# analog.net
KiCad netlist of a schematic drawn in Altium Designer
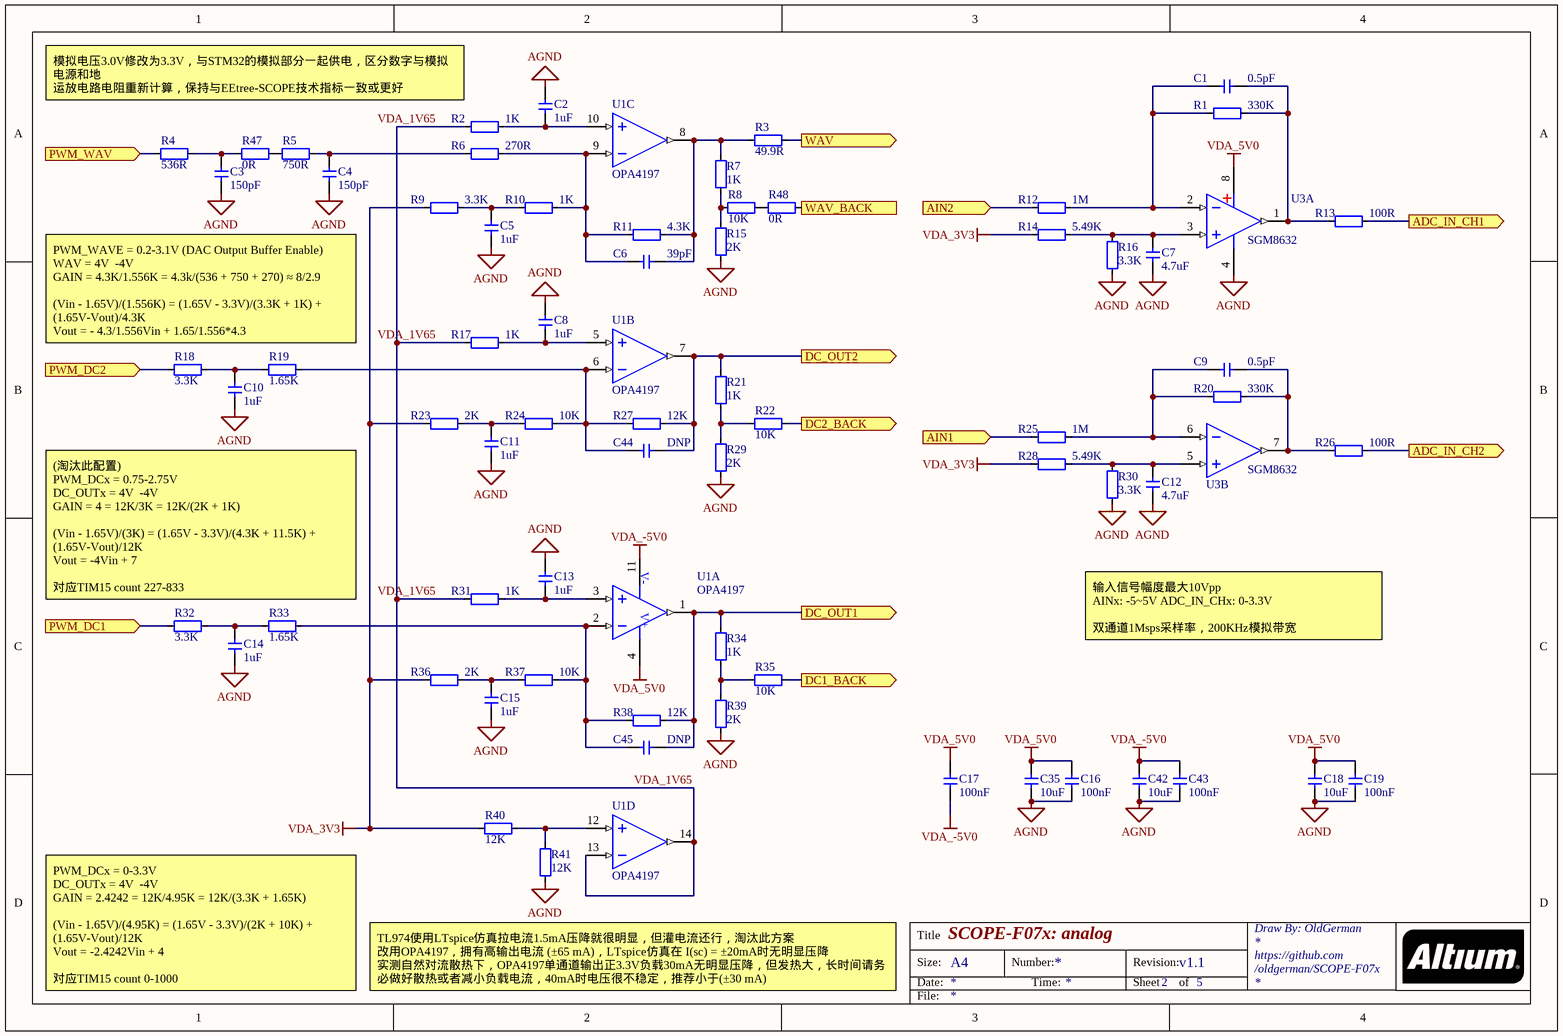
[diagram p0: analog.SchDoc]

(export (version "E")
  (design (tool "Eeschema 10.0.6"))
  (components
    (comp (ref "C1")
      (value "0.5pF")
      (footprint "C0402")
      (description "Capacitor")
      (libsource (lib "ODG_AD_Lib") (part "CAP"))
    )
    (comp (ref "C2")
      (value "1uF")
      (footprint "C0402")
      (description "Capacitor")
      (libsource (lib "ODG_AD_Lib") (part "CAP"))
    )
    (comp (ref "C3")
      (value "150pF")
      (footprint "C0402")
      (description "Capacitor")
      (libsource (lib "ODG_AD_Lib") (part "CAP"))
    )
    (comp (ref "C4")
      (value "150pF")
      (footprint "C0402")
      (description "Capacitor")
      (libsource (lib "ODG_AD_Lib") (part "CAP"))
    )
    (comp (ref "C5")
      (value "1uF")
      (footprint "C0402")
      (description "Capacitor")
      (libsource (lib "ODG_AD_Lib") (part "CAP"))
    )
    (comp (ref "C6")
      (value "39pF")
      (footprint "C0402")
      (description "Capacitor")
      (libsource (lib "ODG_AD_Lib") (part "CAP"))
    )
    (comp (ref "C7")
      (value "4.7uF")
      (footprint "C0402")
      (description "Capacitor")
      (libsource (lib "ODG_AD_Lib") (part "CAP"))
    )
    (comp (ref "C8")
      (value "1uF")
      (footprint "C0402")
      (description "Capacitor")
      (libsource (lib "ODG_AD_Lib") (part "CAP"))
    )
    (comp (ref "C9")
      (value "0.5pF")
      (footprint "C0402")
      (description "Capacitor")
      (libsource (lib "ODG_AD_Lib") (part "CAP"))
    )
    (comp (ref "C10")
      (value "1uF")
      (footprint "C0402")
      (description "Capacitor")
      (libsource (lib "ODG_AD_Lib") (part "CAP"))
    )
    (comp (ref "C11")
      (value "1uF")
      (footprint "C0402")
      (description "Capacitor")
      (libsource (lib "ODG_AD_Lib") (part "CAP"))
    )
    (comp (ref "C12")
      (value "4.7uF")
      (footprint "C0402")
      (description "Capacitor")
      (libsource (lib "ODG_AD_Lib") (part "CAP"))
    )
    (comp (ref "C13")
      (value "1uF")
      (footprint "C0402")
      (description "Capacitor")
      (libsource (lib "ODG_AD_Lib") (part "CAP"))
    )
    (comp (ref "C14")
      (value "1uF")
      (footprint "C0402")
      (description "Capacitor")
      (libsource (lib "ODG_AD_Lib") (part "CAP"))
    )
    (comp (ref "C15")
      (value "1uF")
      (footprint "C0402")
      (description "Capacitor")
      (libsource (lib "ODG_AD_Lib") (part "CAP"))
    )
    (comp (ref "C16")
      (value "100nF")
      (footprint "C0402")
      (description "Capacitor")
      (libsource (lib "ODG_AD_Lib") (part "CAP"))
    )
    (comp (ref "C17")
      (value "100nF")
      (footprint "C0402")
      (description "Capacitor")
      (libsource (lib "ODG_AD_Lib") (part "CAP"))
    )
    (comp (ref "C18")
      (value "10uF")
      (footprint "C0402")
      (description "Capacitor")
      (libsource (lib "ODG_AD_Lib") (part "CAP"))
    )
    (comp (ref "C19")
      (value "100nF")
      (footprint "C0402")
      (description "Capacitor")
      (libsource (lib "ODG_AD_Lib") (part "CAP"))
    )
    (comp (ref "C35")
      (value "10uF")
      (footprint "C0402")
      (description "Capacitor")
      (libsource (lib "ODG_AD_Lib") (part "CAP"))
    )
    (comp (ref "C42")
      (value "10uF")
      (footprint "C0402")
      (description "Capacitor")
      (libsource (lib "ODG_AD_Lib") (part "CAP"))
    )
    (comp (ref "C43")
      (value "100nF")
      (footprint "C0402")
      (description "Capacitor")
      (libsource (lib "ODG_AD_Lib") (part "CAP"))
    )
    (comp (ref "C44")
      (value "DNP")
      (footprint "C0402")
      (description "Capacitor")
      (libsource (lib "ODG_AD_Lib") (part "CAP"))
    )
    (comp (ref "C45")
      (value "DNP")
      (footprint "C0402")
      (description "Capacitor")
      (libsource (lib "ODG_AD_Lib") (part "CAP"))
    )
    (comp (ref "R1")
      (value "330K")
      (footprint "R0402")
      (description "Resistor")
      (libsource (lib "ODG_AD_Lib") (part "RES"))
    )
    (comp (ref "R2")
      (value "1K")
      (footprint "R0402")
      (description "Resistor")
      (libsource (lib "ODG_AD_Lib") (part "RES"))
    )
    (comp (ref "R3")
      (value "49.9R")
      (footprint "R0402")
      (description "Resistor")
      (libsource (lib "ODG_AD_Lib") (part "RES"))
    )
    (comp (ref "R4")
      (value "536R")
      (footprint "R0402")
      (description "Resistor")
      (libsource (lib "ODG_AD_Lib") (part "RES"))
    )
    (comp (ref "R5")
      (value "750R")
      (footprint "R0402")
      (description "Resistor")
      (libsource (lib "ODG_AD_Lib") (part "RES"))
    )
    (comp (ref "R6")
      (value "270R")
      (footprint "R0402")
      (description "Resistor")
      (libsource (lib "ODG_AD_Lib") (part "RES"))
    )
    (comp (ref "R7")
      (value "1K")
      (footprint "R0402")
      (description "Resistor")
      (libsource (lib "") (part "RES_1"))
    )
    (comp (ref "R8")
      (value "10K")
      (footprint "R0402")
      (description "Resistor")
      (libsource (lib "") (part "RES_2"))
    )
    (comp (ref "R9")
      (value "3.3K")
      (footprint "R0402")
      (description "Resistor")
      (libsource (lib "ODG_AD_Lib") (part "RES"))
    )
    (comp (ref "R10")
      (value "1K")
      (footprint "R0402")
      (description "Resistor")
      (libsource (lib "ODG_AD_Lib") (part "RES"))
    )
    (comp (ref "R11")
      (value "4.3K")
      (footprint "R0402")
      (description "Resistor")
      (libsource (lib "ODG_AD_Lib") (part "RES"))
    )
    (comp (ref "R12")
      (value "1M")
      (footprint "R0402")
      (description "Resistor")
      (libsource (lib "ODG_AD_Lib") (part "RES"))
    )
    (comp (ref "R13")
      (value "100R")
      (footprint "R0402")
      (description "Resistor")
      (libsource (lib "ODG_AD_Lib") (part "RES"))
    )
    (comp (ref "R14")
      (value "5.49K")
      (footprint "R0402")
      (description "Resistor")
      (libsource (lib "ODG_AD_Lib") (part "RES"))
    )
    (comp (ref "R15")
      (value "2K")
      (footprint "R0402")
      (description "Resistor")
      (libsource (lib "") (part "RES_1"))
    )
    (comp (ref "R16")
      (value "3.3K")
      (footprint "R0402")
      (description "Resistor")
      (libsource (lib "") (part "RES_1"))
    )
    (comp (ref "R17")
      (value "1K")
      (footprint "R0402")
      (description "Resistor")
      (libsource (lib "ODG_AD_Lib") (part "RES"))
    )
    (comp (ref "R18")
      (value "3.3K")
      (footprint "R0402")
      (description "Resistor")
      (libsource (lib "ODG_AD_Lib") (part "RES"))
    )
    (comp (ref "R19")
      (value "1.65K")
      (footprint "R0402")
      (description "Resistor")
      (libsource (lib "ODG_AD_Lib") (part "RES"))
    )
    (comp (ref "R20")
      (value "330K")
      (footprint "R0402")
      (description "Resistor")
      (libsource (lib "ODG_AD_Lib") (part "RES"))
    )
    (comp (ref "R21")
      (value "1K")
      (footprint "R0402")
      (description "Resistor")
      (libsource (lib "") (part "RES_1"))
    )
    (comp (ref "R22")
      (value "10K")
      (footprint "R0402")
      (description "Resistor")
      (libsource (lib "") (part "RES_2"))
    )
    (comp (ref "R23")
      (value "2K")
      (footprint "R0402")
      (description "Resistor")
      (libsource (lib "ODG_AD_Lib") (part "RES"))
    )
    (comp (ref "R24")
      (value "10K")
      (footprint "R0402")
      (description "Resistor")
      (libsource (lib "ODG_AD_Lib") (part "RES"))
    )
    (comp (ref "R25")
      (value "1M")
      (footprint "R0402")
      (description "Resistor")
      (libsource (lib "ODG_AD_Lib") (part "RES"))
    )
    (comp (ref "R26")
      (value "100R")
      (footprint "R0402")
      (description "Resistor")
      (libsource (lib "ODG_AD_Lib") (part "RES"))
    )
    (comp (ref "R27")
      (value "12K")
      (footprint "R0402")
      (description "Resistor")
      (libsource (lib "ODG_AD_Lib") (part "RES"))
    )
    (comp (ref "R28")
      (value "5.49K")
      (footprint "R0402")
      (description "Resistor")
      (libsource (lib "ODG_AD_Lib") (part "RES"))
    )
    (comp (ref "R29")
      (value "2K")
      (footprint "R0402")
      (description "Resistor")
      (libsource (lib "") (part "RES_1"))
    )
    (comp (ref "R30")
      (value "3.3K")
      (footprint "R0402")
      (description "Resistor")
      (libsource (lib "") (part "RES_1"))
    )
    (comp (ref "R31")
      (value "1K")
      (footprint "R0402")
      (description "Resistor")
      (libsource (lib "ODG_AD_Lib") (part "RES"))
    )
    (comp (ref "R32")
      (value "3.3K")
      (footprint "R0402")
      (description "Resistor")
      (libsource (lib "ODG_AD_Lib") (part "RES"))
    )
    (comp (ref "R33")
      (value "1.65K")
      (footprint "R0402")
      (description "Resistor")
      (libsource (lib "ODG_AD_Lib") (part "RES"))
    )
    (comp (ref "R34")
      (value "1K")
      (footprint "R0402")
      (description "Resistor")
      (libsource (lib "") (part "RES_1"))
    )
    (comp (ref "R35")
      (value "10K")
      (footprint "R0402")
      (description "Resistor")
      (libsource (lib "") (part "RES_2"))
    )
    (comp (ref "R36")
      (value "2K")
      (footprint "R0402")
      (description "Resistor")
      (libsource (lib "ODG_AD_Lib") (part "RES"))
    )
    (comp (ref "R37")
      (value "10K")
      (footprint "R0402")
      (description "Resistor")
      (libsource (lib "ODG_AD_Lib") (part "RES"))
    )
    (comp (ref "R38")
      (value "12K")
      (footprint "R0402")
      (description "Resistor")
      (libsource (lib "ODG_AD_Lib") (part "RES"))
    )
    (comp (ref "R39")
      (value "2K")
      (footprint "R0402")
      (description "Resistor")
      (libsource (lib "") (part "RES_1"))
    )
    (comp (ref "R40")
      (value "12K")
      (footprint "R0402")
      (description "Resistor")
      (libsource (lib "ODG_AD_Lib") (part "RES"))
    )
    (comp (ref "R41")
      (value "12K")
      (footprint "R0402")
      (description "Resistor")
      (libsource (lib "") (part "RES_1"))
    )
    (comp (ref "R47")
      (value "0R")
      (footprint "R0805")
      (description "Resistor")
      (libsource (lib "ODG_AD_Lib") (part "RES"))
    )
    (comp (ref "R48")
      (value "0R")
      (footprint "R0805")
      (description "Resistor")
      (libsource (lib "ODG_AD_Lib") (part "RES"))
    )
    (comp (ref "U1")
      (value "OPA4197")
      (footprint "ON SEMI TSSOP-14 948G")
      (fields
        (field (name "PART NUMBER") "ADA4622-4")
        (field (name "MANUFACTURER") "Analog Devices")
        (field (name "MANUFACTURER PART NUMBER") "ADA4622-4ACPZ-RL")
        (field (name "PUBLISHER") "Nordic Semiconductor")
      )
      (libsource (lib "ODG_Project") (part "OPA4140AIPWR"))
    )
    (comp (ref "U3")
      (value "SGM8632")
      (footprint "ANALOG DEV SOIC-8 R8")
      (fields (field (name "版权归属") "源创客"))
      (libsource (lib "ODG_AD_Lib") (part "AD8542"))
    )
  )
  (nets
    (net (code "1") (name "/ADC_IN_CH1") (class "Default")
      (node (ref "R13") (pin "2") (pinfunction "2_2") (pintype "passive"))
    )
    (net (code "2") (name "/ADC_IN_CH2") (class "Default")
      (node (ref "R26") (pin "2") (pinfunction "2_2") (pintype "passive"))
    )
    (net (code "3") (name "/AIN1") (class "Default")
      (node (ref "R25") (pin "1") (pinfunction "1_1") (pintype "passive"))
    )
    (net (code "4") (name "/AIN2") (class "Default")
      (node (ref "R12") (pin "1") (pinfunction "1_1") (pintype "passive"))
    )
    (net (code "5") (name "/DC1_BACK") (class "Default")
      (node (ref "R35") (pin "1") (pinfunction "1_1") (pintype "passive"))
    )
    (net (code "6") (name "/DC2_BACK") (class "Default")
      (node (ref "R22") (pin "1") (pinfunction "1_1") (pintype "passive"))
    )
    (net (code "7") (name "/DC_OUT1") (class "Default")
      (node (ref "C45") (pin "1") (pinfunction "1_1") (pintype "passive"))
      (node (ref "R34") (pin "2") (pinfunction "2_2") (pintype "passive"))
      (node (ref "R38") (pin "2") (pinfunction "2_2") (pintype "passive"))
      (node (ref "U1") (pin "1") (pinfunction "OUTA_1") (pintype "output"))
    )
    (net (code "8") (name "/DC_OUT2") (class "Default")
      (node (ref "C44") (pin "1") (pinfunction "1_1") (pintype "passive"))
      (node (ref "R21") (pin "2") (pinfunction "2_2") (pintype "passive"))
      (node (ref "R27") (pin "2") (pinfunction "2_2") (pintype "passive"))
      (node (ref "U1") (pin "7") (pinfunction "OUTB_7") (pintype "output"))
    )
    (net (code "9") (name "/PWM_DC1") (class "Default")
      (node (ref "R32") (pin "1") (pinfunction "1_1") (pintype "passive"))
    )
    (net (code "10") (name "/PWM_DC2") (class "Default")
      (node (ref "R18") (pin "1") (pinfunction "1_1") (pintype "passive"))
    )
    (net (code "11") (name "/PWM_WAV") (class "Default")
      (node (ref "R4") (pin "1") (pinfunction "1_1") (pintype "passive"))
    )
    (net (code "12") (name "/VDA_1V65") (class "Default")
      (node (ref "R17") (pin "1") (pinfunction "1_1") (pintype "passive"))
      (node (ref "R2") (pin "1") (pinfunction "1_1") (pintype "passive"))
      (node (ref "R31") (pin "1") (pinfunction "1_1") (pintype "passive"))
      (node (ref "U1") (pin "13") (pinfunction "IN_D-_13") (pintype "input"))
      (node (ref "U1") (pin "14") (pinfunction "OUTD_14") (pintype "output"))
    )
    (net (code "13") (name "/WAV") (class "Default")
      (node (ref "R3") (pin "2") (pinfunction "2_2") (pintype "passive"))
    )
    (net (code "14") (name "/WAV_BACK") (class "Default")
      (node (ref "R48") (pin "2") (pinfunction "2_2") (pintype "passive"))
    )
    (net (code "15") (name "AGND") (class "Default")
      (node (ref "C10") (pin "1") (pinfunction "1_1") (pintype "passive"))
      (node (ref "C11") (pin "1") (pinfunction "1_1") (pintype "passive"))
      (node (ref "C12") (pin "1") (pinfunction "1_1") (pintype "passive"))
      (node (ref "C13") (pin "2") (pinfunction "2_2") (pintype "passive"))
      (node (ref "C14") (pin "1") (pinfunction "1_1") (pintype "passive"))
      (node (ref "C15") (pin "1") (pinfunction "1_1") (pintype "passive"))
      (node (ref "C16") (pin "1") (pinfunction "1_1") (pintype "passive"))
      (node (ref "C18") (pin "1") (pinfunction "1_1") (pintype "passive"))
      (node (ref "C19") (pin "1") (pinfunction "1_1") (pintype "passive"))
      (node (ref "C2") (pin "2") (pinfunction "2_2") (pintype "passive"))
      (node (ref "C3") (pin "1") (pinfunction "1_1") (pintype "passive"))
      (node (ref "C35") (pin "1") (pinfunction "1_1") (pintype "passive"))
      (node (ref "C4") (pin "1") (pinfunction "1_1") (pintype "passive"))
      (node (ref "C42") (pin "1") (pinfunction "1_1") (pintype "passive"))
      (node (ref "C43") (pin "1") (pinfunction "1_1") (pintype "passive"))
      (node (ref "C5") (pin "1") (pinfunction "1_1") (pintype "passive"))
      (node (ref "C7") (pin "1") (pinfunction "1_1") (pintype "passive"))
      (node (ref "C8") (pin "2") (pinfunction "2_2") (pintype "passive"))
      (node (ref "R15") (pin "1") (pinfunction "1_1") (pintype "passive"))
      (node (ref "R16") (pin "1") (pinfunction "1_1") (pintype "passive"))
      (node (ref "R29") (pin "1") (pinfunction "1_1") (pintype "passive"))
      (node (ref "R30") (pin "1") (pinfunction "1_1") (pintype "passive"))
      (node (ref "R39") (pin "1") (pinfunction "1_1") (pintype "passive"))
      (node (ref "R41") (pin "1") (pinfunction "1_1") (pintype "passive"))
      (node (ref "U3") (pin "4") (pinfunction "V-_4") (pintype "power_in"))
    )
    (net (code "16") (name "Net-(C3-Pad2)") (class "Default")
      (node (ref "C3") (pin "2") (pinfunction "2_2") (pintype "passive"))
      (node (ref "R4") (pin "2") (pinfunction "2_2") (pintype "passive"))
      (node (ref "R47") (pin "1") (pinfunction "1_1") (pintype "passive"))
    )
    (net (code "17") (name "Net-(C4-Pad2)") (class "Default")
      (node (ref "C4") (pin "2") (pinfunction "2_2") (pintype "passive"))
      (node (ref "R5") (pin "2") (pinfunction "2_2") (pintype "passive"))
      (node (ref "R6") (pin "1") (pinfunction "1_1") (pintype "passive"))
    )
    (net (code "18") (name "Net-(C5-Pad2)") (class "Default")
      (node (ref "C5") (pin "2") (pinfunction "2_2") (pintype "passive"))
      (node (ref "R10") (pin "1") (pinfunction "1_1") (pintype "passive"))
      (node (ref "R9") (pin "2") (pinfunction "2_2") (pintype "passive"))
    )
    (net (code "19") (name "Net-(C10-Pad2)") (class "Default")
      (node (ref "C10") (pin "2") (pinfunction "2_2") (pintype "passive"))
      (node (ref "R18") (pin "2") (pinfunction "2_2") (pintype "passive"))
      (node (ref "R19") (pin "1") (pinfunction "1_1") (pintype "passive"))
    )
    (net (code "20") (name "Net-(C11-Pad2)") (class "Default")
      (node (ref "C11") (pin "2") (pinfunction "2_2") (pintype "passive"))
      (node (ref "R23") (pin "2") (pinfunction "2_2") (pintype "passive"))
      (node (ref "R24") (pin "1") (pinfunction "1_1") (pintype "passive"))
    )
    (net (code "21") (name "Net-(C14-Pad2)") (class "Default")
      (node (ref "C14") (pin "2") (pinfunction "2_2") (pintype "passive"))
      (node (ref "R32") (pin "2") (pinfunction "2_2") (pintype "passive"))
      (node (ref "R33") (pin "1") (pinfunction "1_1") (pintype "passive"))
    )
    (net (code "22") (name "Net-(C15-Pad2)") (class "Default")
      (node (ref "C15") (pin "2") (pinfunction "2_2") (pintype "passive"))
      (node (ref "R36") (pin "2") (pinfunction "2_2") (pintype "passive"))
      (node (ref "R37") (pin "1") (pinfunction "1_1") (pintype "passive"))
    )
    (net (code "23") (name "Net-(R15-Pad2)") (class "Default")
      (node (ref "R15") (pin "2") (pinfunction "2_2") (pintype "passive"))
      (node (ref "R7") (pin "1") (pinfunction "1_1") (pintype "passive"))
      (node (ref "R8") (pin "2") (pinfunction "2_2") (pintype "passive"))
    )
    (net (code "24") (name "Net-(R21-Pad1)") (class "Default")
      (node (ref "R21") (pin "1") (pinfunction "1_1") (pintype "passive"))
      (node (ref "R22") (pin "2") (pinfunction "2_2") (pintype "passive"))
      (node (ref "R29") (pin "2") (pinfunction "2_2") (pintype "passive"))
    )
    (net (code "25") (name "Net-(R34-Pad1)") (class "Default")
      (node (ref "R34") (pin "1") (pinfunction "1_1") (pintype "passive"))
      (node (ref "R35") (pin "2") (pinfunction "2_2") (pintype "passive"))
      (node (ref "R39") (pin "2") (pinfunction "2_2") (pintype "passive"))
    )
    (net (code "26") (name "Net-(R47-Pad2)") (class "Default")
      (node (ref "R47") (pin "2") (pinfunction "2_2") (pintype "passive"))
      (node (ref "R5") (pin "1") (pinfunction "1_1") (pintype "passive"))
    )
    (net (code "27") (name "Net-(R48-Pad1)") (class "Default")
      (node (ref "R48") (pin "1") (pinfunction "1_1") (pintype "passive"))
      (node (ref "R8") (pin "1") (pinfunction "1_1") (pintype "passive"))
    )
    (net (code "28") (name "Net-(U1A-IN_A+)") (class "Default")
      (node (ref "C13") (pin "1") (pinfunction "1_1") (pintype "passive"))
      (node (ref "R31") (pin "2") (pinfunction "2_2") (pintype "passive"))
      (node (ref "U1") (pin "3") (pinfunction "IN_A+_3") (pintype "input"))
    )
    (net (code "29") (name "Net-(U1A-IN_A-)") (class "Default")
      (node (ref "C45") (pin "2") (pinfunction "2_2") (pintype "passive"))
      (node (ref "R33") (pin "2") (pinfunction "2_2") (pintype "passive"))
      (node (ref "R37") (pin "2") (pinfunction "2_2") (pintype "passive"))
      (node (ref "R38") (pin "1") (pinfunction "1_1") (pintype "passive"))
      (node (ref "U1") (pin "2") (pinfunction "IN_A-_2") (pintype "input"))
    )
    (net (code "30") (name "Net-(U1B-IN_B+)") (class "Default")
      (node (ref "C8") (pin "1") (pinfunction "1_1") (pintype "passive"))
      (node (ref "R17") (pin "2") (pinfunction "2_2") (pintype "passive"))
      (node (ref "U1") (pin "5") (pinfunction "IN_B+_5") (pintype "input"))
    )
    (net (code "31") (name "Net-(U1B-IN_B-)") (class "Default")
      (node (ref "C44") (pin "2") (pinfunction "2_2") (pintype "passive"))
      (node (ref "R19") (pin "2") (pinfunction "2_2") (pintype "passive"))
      (node (ref "R24") (pin "2") (pinfunction "2_2") (pintype "passive"))
      (node (ref "R27") (pin "1") (pinfunction "1_1") (pintype "passive"))
      (node (ref "U1") (pin "6") (pinfunction "IN_B-_6") (pintype "input"))
    )
    (net (code "32") (name "Net-(U1C-IN_C+)") (class "Default")
      (node (ref "C2") (pin "1") (pinfunction "1_1") (pintype "passive"))
      (node (ref "R2") (pin "2") (pinfunction "2_2") (pintype "passive"))
      (node (ref "U1") (pin "10") (pinfunction "IN_C+_10") (pintype "input"))
    )
    (net (code "33") (name "Net-(U1C-IN_C-)") (class "Default")
      (node (ref "C6") (pin "2") (pinfunction "2_2") (pintype "passive"))
      (node (ref "R10") (pin "2") (pinfunction "2_2") (pintype "passive"))
      (node (ref "R11") (pin "1") (pinfunction "1_1") (pintype "passive"))
      (node (ref "R6") (pin "2") (pinfunction "2_2") (pintype "passive"))
      (node (ref "U1") (pin "9") (pinfunction "IN_C-_9") (pintype "input"))
    )
    (net (code "34") (name "Net-(U1C-OUTC)") (class "Default")
      (node (ref "C6") (pin "1") (pinfunction "1_1") (pintype "passive"))
      (node (ref "R11") (pin "2") (pinfunction "2_2") (pintype "passive"))
      (node (ref "R3") (pin "1") (pinfunction "1_1") (pintype "passive"))
      (node (ref "R7") (pin "2") (pinfunction "2_2") (pintype "passive"))
      (node (ref "U1") (pin "8") (pinfunction "OUTC_8") (pintype "output"))
    )
    (net (code "35") (name "Net-(U1D-IN_D+)") (class "Default")
      (node (ref "R40") (pin "2") (pinfunction "2_2") (pintype "passive"))
      (node (ref "R41") (pin "2") (pinfunction "2_2") (pintype "passive"))
      (node (ref "U1") (pin "12") (pinfunction "IN_D+_12") (pintype "input"))
    )
    (net (code "36") (name "Net-(U3A-+)") (class "Default")
      (node (ref "C7") (pin "2") (pinfunction "2_2") (pintype "passive"))
      (node (ref "R14") (pin "2") (pinfunction "2_2") (pintype "passive"))
      (node (ref "R16") (pin "2") (pinfunction "2_2") (pintype "passive"))
      (node (ref "U3") (pin "3") (pinfunction "+_3") (pintype "input"))
    )
    (net (code "37") (name "Net-(U3A--)") (class "Default")
      (node (ref "C1") (pin "2") (pinfunction "2_2") (pintype "passive"))
      (node (ref "R1") (pin "1") (pinfunction "1_1") (pintype "passive"))
      (node (ref "R12") (pin "2") (pinfunction "2_2") (pintype "passive"))
      (node (ref "U3") (pin "2") (pinfunction "-_2") (pintype "input"))
    )
    (net (code "38") (name "Net-(U3A-OUT1)") (class "Default")
      (node (ref "C1") (pin "1") (pinfunction "1_1") (pintype "passive"))
      (node (ref "R1") (pin "2") (pinfunction "2_2") (pintype "passive"))
      (node (ref "R13") (pin "1") (pinfunction "1_1") (pintype "passive"))
      (node (ref "U3") (pin "1") (pinfunction "OUT1_1") (pintype "output"))
    )
    (net (code "39") (name "Net-(U3B-+)") (class "Default")
      (node (ref "C12") (pin "2") (pinfunction "2_2") (pintype "passive"))
      (node (ref "R28") (pin "2") (pinfunction "2_2") (pintype "passive"))
      (node (ref "R30") (pin "2") (pinfunction "2_2") (pintype "passive"))
      (node (ref "U3") (pin "5") (pinfunction "+_5") (pintype "input"))
    )
    (net (code "40") (name "Net-(U3B--)") (class "Default")
      (node (ref "C9") (pin "2") (pinfunction "2_2") (pintype "passive"))
      (node (ref "R20") (pin "1") (pinfunction "1_1") (pintype "passive"))
      (node (ref "R25") (pin "2") (pinfunction "2_2") (pintype "passive"))
      (node (ref "U3") (pin "6") (pinfunction "-_6") (pintype "input"))
    )
    (net (code "41") (name "Net-(U3B-OUT2)") (class "Default")
      (node (ref "C9") (pin "1") (pinfunction "1_1") (pintype "passive"))
      (node (ref "R20") (pin "2") (pinfunction "2_2") (pintype "passive"))
      (node (ref "R26") (pin "1") (pinfunction "1_1") (pintype "passive"))
      (node (ref "U3") (pin "7") (pinfunction "OUT2_7") (pintype "output"))
    )
    (net (code "42") (name "VDA_-5V0") (class "Default")
      (node (ref "C17") (pin "1") (pinfunction "1_1") (pintype "passive"))
      (node (ref "C42") (pin "2") (pinfunction "2_2") (pintype "passive"))
      (node (ref "C43") (pin "2") (pinfunction "2_2") (pintype "passive"))
      (node (ref "U1") (pin "11") (pinfunction "VSS_11") (pintype "power_in"))
    )
    (net (code "43") (name "VDA_3V3") (class "Default")
      (node (ref "R14") (pin "1") (pinfunction "1_1") (pintype "passive"))
      (node (ref "R23") (pin "1") (pinfunction "1_1") (pintype "passive"))
      (node (ref "R28") (pin "1") (pinfunction "1_1") (pintype "passive"))
      (node (ref "R36") (pin "1") (pinfunction "1_1") (pintype "passive"))
      (node (ref "R40") (pin "1") (pinfunction "1_1") (pintype "passive"))
      (node (ref "R9") (pin "1") (pinfunction "1_1") (pintype "passive"))
    )
    (net (code "44") (name "VDA_5V0") (class "Default")
      (node (ref "C16") (pin "2") (pinfunction "2_2") (pintype "passive"))
      (node (ref "C17") (pin "2") (pinfunction "2_2") (pintype "passive"))
      (node (ref "C18") (pin "2") (pinfunction "2_2") (pintype "passive"))
      (node (ref "C19") (pin "2") (pinfunction "2_2") (pintype "passive"))
      (node (ref "C35") (pin "2") (pinfunction "2_2") (pintype "passive"))
      (node (ref "U1") (pin "4") (pinfunction "VDD_4") (pintype "power_in"))
      (node (ref "U3") (pin "8") (pinfunction "V+_8") (pintype "power_in"))
    )
  )
)
